# CHARGER_2A.net
KiCad netlist of a schematic drawn in Altium Designer
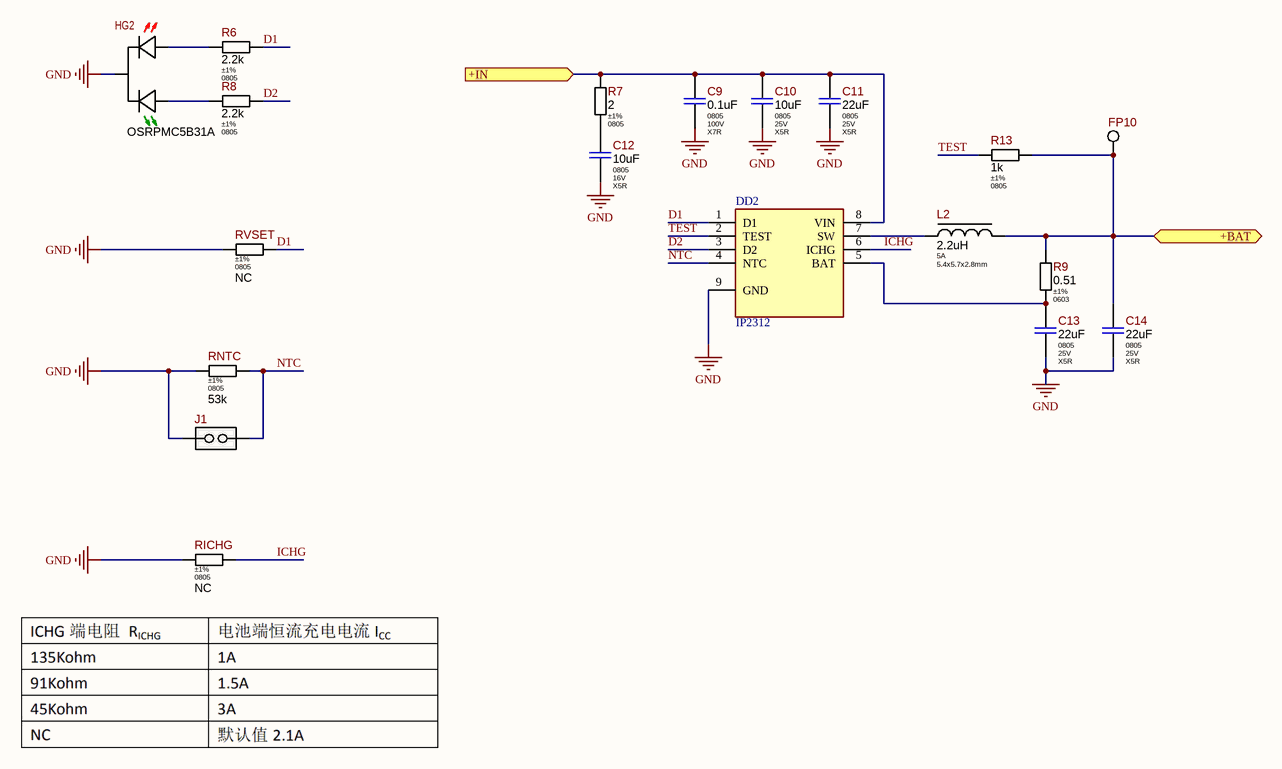
[diagram p0: CHARGER_2A.SchDoc]

(export (version "E")
  (design (tool "Eeschema 10.0.6"))
  (components
    (comp (ref "C9")
      (value "0.1uF")
      (footprint "C_CERAMIC_0805_MED")
      (description "100nF 100V X7R ±10% 0805 Ceramic Capacitor RoHS")
      (fields
        (field (name "PACKAGE") "0805")
        (field (name "VOLTAGE") "100V")
        (field (name "DIELECTRIC TYPE") "X7R")
        (field (name "PART NUMBER") "CL21B104KCFSFNE")
        (field (name "MANUFACTURER") "Samsung Electro-Mechanics")
      )
      (libsource (lib "capacitors") (part "CL21B104KCFSFNE"))
    )
    (comp (ref "C10")
      (value "10uF")
      (footprint "CAP-0805(2012)X85T10")
      (description "10uF 25V X5R ±20% 0805 Ceramic Capacitor RoHS")
      (fields
        (field (name "PACKAGE") "0805")
        (field (name "VOLTAGE") "25V")
        (field (name "DIELECTRIC TYPE") "X5R")
        (field (name "PART NUMBER") "C2012X5R1E106M085AC")
        (field (name "MANUFACTURER") "TDK Corporation")
      )
      (libsource (lib "capacitors") (part "C2012X5R1E106M085AC"))
    )
    (comp (ref "C11")
      (value "22uF")
      (footprint "CAP-0805(2012)X125T15")
      (description "22uF 25V X5R ±20% 0805 Ceramic Capacitor RoHS")
      (fields
        (field (name "PACKAGE") "0805")
        (field (name "VOLTAGE") "25V")
        (field (name "DIELECTRIC TYPE") "X5R")
        (field (name "PART NUMBER") "CL21A226MAQNNNE")
        (field (name "MANUFACTURER") "Samsung Electro-Mechanics")
      )
      (libsource (lib "capacitors") (part "CL21A226MAQNNNE"))
    )
    (comp (ref "C12")
      (value "10uF")
      (footprint "CAP-0805(2012)X125T15")
      (description "10uF 16V Х5R ±10% 0805 Ceramic Capacitor RoHS")
      (fields
        (field (name "PACKAGE") "0805")
        (field (name "VOLTAGE") "16V")
        (field (name "DIELECTRIC TYPE") "X5R")
        (field (name "PART NUMBER") "CL21A106KOQNNNE")
        (field (name "MANUFACTURER") "Samsung Electro-Mechanics")
      )
      (libsource (lib "capacitors") (part "CL21A106KOQNNNE"))
    )
    (comp (ref "C13")
      (value "22uF")
      (footprint "CAP-0805(2012)X125T15")
      (description "22uF 25V X5R ±20% 0805 Ceramic Capacitor RoHS")
      (fields
        (field (name "PACKAGE") "0805")
        (field (name "VOLTAGE") "25V")
        (field (name "DIELECTRIC TYPE") "X5R")
        (field (name "PART NUMBER") "CL21A226MAQNNNE")
        (field (name "MANUFACTURER") "Samsung Electro-Mechanics")
      )
      (libsource (lib "capacitors") (part "CL21A226MAQNNNE"))
    )
    (comp (ref "C14")
      (value "22uF")
      (footprint "CAP-0805(2012)X125T15")
      (description "22uF 25V X5R ±20% 0805 Ceramic Capacitor RoHS")
      (fields
        (field (name "PACKAGE") "0805")
        (field (name "VOLTAGE") "25V")
        (field (name "DIELECTRIC TYPE") "X5R")
        (field (name "PART NUMBER") "CL21A226MAQNNNE")
        (field (name "MANUFACTURER") "Samsung Electro-Mechanics")
      )
      (libsource (lib "capacitors") (part "CL21A226MAQNNNE"))
    )
    (comp (ref "DD2") (value "IP2312") (footprint "IP2313") (libsource (lib "vitech_lib") (part "IP2312")))
    (comp (ref "FP10")
      (value "PAD-1.45mm")
      (footprint "PAD-1.45mm")
      (description "1.45mm Pad for Plug-In or Receptacle")
      (fields (field (name "MANUFACTURER") "NONE"))
      (libsource (lib "probetools") (part "PAD-1.45mm"))
    )
    (comp (ref "HG2")
      (value "OSRPMC5B31A")
      (footprint "OSRPMC5B31A")
      (description "5mm Phoenix Red & Pure Green LED, 625nm and 525nm, 30°")
      (fields (field (name "PART NUMBER") "OSRPMC5B31A") (field (name "MANUFACTURER") "OptoSupply"))
      (libsource (lib "opto") (part "OSRPMC5B31A"))
    )
    (comp (ref "J1")
      (value "PLS-2 (Part of PLS-40)")
      (footprint "PLS-2")
      (description "2 Pin 2.54mm Male Header, Vertical, 3mm and 6.1mm, PLS-2")
      (fields (field (name "PART NUMBER") "DS1021-02SF11") (field (name "MANUFACTURER") "Connfly"))
      (libsource (lib "connectors") (part "DS1021-02SF11"))
    )
    (comp (ref "L2")
      (value "2.2uH")
      (footprint "BMRA00050530-Series")
      (description "2.2uH 5A 35mOhm max Closed Magnetic, Molding Processing, Ultra High Current Power Inductor")
      (fields
        (field (name "CURRENT") "5A")
        (field (name "PACKAGE") "5.4x5.7x2.8mm")
        (field (name "PART NUMBER") "BMRA000505302R2MA1")
        (field (name "TOLERANCE") "±20%")
      )
      (libsource (lib "inductors") (part "BMRA000505302R2MA1"))
    )
    (comp (ref "R6")
      (value "2.2k")
      (footprint "R_ANY_CHIP_0805_MED")
      (description "2.2 kOhms ±1% 1/8W 0805 Thick Film Resistor")
      (fields
        (field (name "TOLERANCE") "±1%")
        (field (name "PACKAGE") "0805")
        (field (name "PART NUMBER") "RC0805FR-072K2L")
        (field (name "MANUFACTURER") "Yageo")
      )
      (libsource (lib "resistors") (part "RC0805FR-072K2L"))
    )
    (comp (ref "R7")
      (value "2")
      (footprint "R_ANY_CHIP_0805_MED")
      (description "2 Ohm ±1%, 1/8W 0805 Thick Film Resistor")
      (fields
        (field (name "TOLERANCE") "±1%")
        (field (name "PACKAGE") "0805")
        (field (name "PART NUMBER") "RC0805FR-072RL")
        (field (name "MANUFACTURER") "Yageo")
      )
      (libsource (lib "resistors") (part "RC0805FR-072RL"))
    )
    (comp (ref "R8")
      (value "2.2k")
      (footprint "R_ANY_CHIP_0805_MED")
      (description "2.2 kOhms ±1% 1/8W 0805 Thick Film Resistor")
      (fields
        (field (name "TOLERANCE") "±1%")
        (field (name "PACKAGE") "0805")
        (field (name "PART NUMBER") "RC0805FR-072K2L")
        (field (name "MANUFACTURER") "Yageo")
      )
      (libsource (lib "resistors") (part "RC0805FR-072K2L"))
    )
    (comp (ref "R9")
      (value "0.51")
      (footprint "R_ANY_CHIP_0603_MED")
      (description "510 mOhms ±1%, 1/10W 0603 Thick Film Resistor")
      (fields
        (field (name "TOLERANCE") "±1%")
        (field (name "PACKAGE") "0603")
        (field (name "PART NUMBER") "RL0603FR-070R51L")
        (field (name "MANUFACTURER") "Yageo")
      )
      (libsource (lib "resistors") (part "RL0603FR-070R51L"))
    )
    (comp (ref "R13")
      (value "1k")
      (footprint "R_ANY_CHIP_0805_MED")
      (description "1 kOhms ±1%, 1/8W 0805 Thick Film Resistor")
      (fields
        (field (name "TOLERANCE") "±1%")
        (field (name "PACKAGE") "0805")
        (field (name "PART NUMBER") "RC0805FR-071KL")
        (field (name "MANUFACTURER") "Yageo")
      )
      (libsource (lib "resistors") (part "RC0805FR-071KL"))
    )
    (comp (ref "RICHG")
      (value "NC")
      (footprint "R_ANY_CHIP_0805_MED")
      (fields
        (field (name "TOLERANCE") "±1%")
        (field (name "PACKAGE") "0805")
        (field (name "PART NUMBER") "RC0805FR-07120RL")
        (field (name "MANUFACTURER") "Yageo")
        (field (name "VOLTAGE") "150V")
      )
      (libsource (lib "resistors") (part "RC0805FR-07120RL"))
    )
    (comp (ref "RNTC")
      (value "53k")
      (footprint "R_ANY_CHIP_0805_MED")
      (fields
        (field (name "TOLERANCE") "±1%")
        (field (name "PACKAGE") "0805")
        (field (name "PART NUMBER") "RC0805FR-07120RL")
        (field (name "MANUFACTURER") "Yageo")
        (field (name "VOLTAGE") "150V")
      )
      (libsource (lib "resistors") (part "RC0805FR-07120RL"))
    )
    (comp (ref "RVSET")
      (value "NC")
      (footprint "R_ANY_CHIP_0805_MED")
      (fields
        (field (name "TOLERANCE") "±1%")
        (field (name "PACKAGE") "0805")
        (field (name "PART NUMBER") "RC0805FR-07120RL")
        (field (name "MANUFACTURER") "Yageo")
        (field (name "VOLTAGE") "150V")
      )
      (libsource (lib "resistors") (part "RC0805FR-07120RL"))
    )
  )
  (nets
    (net (code "1") (name "/+BAT") (class "Default")
      (node (ref "C14") (pin "1") (pinfunction "1_1") (pintype "passive"))
      (node (ref "FP10") (pin "1") (pintype "passive"))
      (node (ref "L2") (pin "2") (pintype "passive"))
      (node (ref "R13") (pin "2") (pintype "passive"))
      (node (ref "R9") (pin "1") (pintype "passive"))
    )
    (net (code "2") (name "/+IN") (class "Default")
      (node (ref "C10") (pin "1") (pinfunction "1_1") (pintype "passive"))
      (node (ref "C11") (pin "1") (pinfunction "1_1") (pintype "passive"))
      (node (ref "C9") (pin "1") (pinfunction "1_1") (pintype "passive"))
      (node (ref "DD2") (pin "8") (pinfunction "VIN_8") (pintype "passive"))
      (node (ref "R7") (pin "1") (pintype "passive"))
    )
    (net (code "3") (name "/D1") (class "Default")
      (node (ref "DD2") (pin "1") (pinfunction "D1_1") (pintype "passive"))
      (node (ref "R6") (pin "2") (pintype "passive"))
      (node (ref "RVSET") (pin "2") (pintype "passive"))
    )
    (net (code "4") (name "/D2") (class "Default")
      (node (ref "DD2") (pin "3") (pinfunction "D2_3") (pintype "passive"))
      (node (ref "R8") (pin "2") (pintype "passive"))
    )
    (net (code "5") (name "/ICHG") (class "Default")
      (node (ref "DD2") (pin "6") (pinfunction "ICHG_6") (pintype "passive"))
      (node (ref "RICHG") (pin "2") (pintype "passive"))
    )
    (net (code "6") (name "/NTC") (class "Default")
      (node (ref "DD2") (pin "4") (pinfunction "NTC_4") (pintype "passive"))
      (node (ref "J1") (pin "2") (pintype "passive"))
      (node (ref "RNTC") (pin "2") (pintype "passive"))
    )
    (net (code "7") (name "/TEST") (class "Default")
      (node (ref "DD2") (pin "2") (pinfunction "TEST_2") (pintype "passive"))
      (node (ref "R13") (pin "1") (pintype "passive"))
    )
    (net (code "8") (name "GND") (class "Default")
      (node (ref "C10") (pin "2") (pinfunction "2_2") (pintype "passive"))
      (node (ref "C11") (pin "2") (pinfunction "2_2") (pintype "passive"))
      (node (ref "C12") (pin "2") (pinfunction "2_2") (pintype "passive"))
      (node (ref "C13") (pin "2") (pinfunction "2_2") (pintype "passive"))
      (node (ref "C14") (pin "2") (pinfunction "2_2") (pintype "passive"))
      (node (ref "C9") (pin "2") (pinfunction "2_2") (pintype "passive"))
      (node (ref "DD2") (pin "9") (pinfunction "GND_9") (pintype "passive"))
      (node (ref "HG2") (pin "CC") (pinfunction "Cathode_CC") (pintype "passive"))
      (node (ref "J1") (pin "1") (pintype "passive"))
      (node (ref "RICHG") (pin "1") (pintype "passive"))
      (node (ref "RNTC") (pin "1") (pintype "passive"))
      (node (ref "RVSET") (pin "1") (pintype "passive"))
    )
    (net (code "9") (name "Net-(C12-Pad1)") (class "Default")
      (node (ref "C12") (pin "1") (pinfunction "1_1") (pintype "passive"))
      (node (ref "R7") (pin "2") (pintype "passive"))
    )
    (net (code "10") (name "Net-(DD2-BAT)") (class "Default")
      (node (ref "C13") (pin "1") (pinfunction "1_1") (pintype "passive"))
      (node (ref "DD2") (pin "5") (pinfunction "BAT_5") (pintype "passive"))
      (node (ref "R9") (pin "2") (pintype "passive"))
    )
    (net (code "11") (name "Net-(DD2-SW)") (class "Default")
      (node (ref "DD2") (pin "7") (pinfunction "SW_7") (pintype "passive"))
      (node (ref "L2") (pin "1") (pintype "passive"))
    )
    (net (code "12") (name "Net-(HG2-PadA1)") (class "Default")
      (node (ref "HG2") (pin "A1") (pintype "passive"))
      (node (ref "R6") (pin "1") (pintype "passive"))
    )
    (net (code "13") (name "Net-(HG2-PadA2)") (class "Default")
      (node (ref "HG2") (pin "A2") (pintype "passive"))
      (node (ref "R8") (pin "1") (pintype "passive"))
    )
  )
)
